# Sheet1.net
KiCad netlist of a schematic drawn in Altium Designer
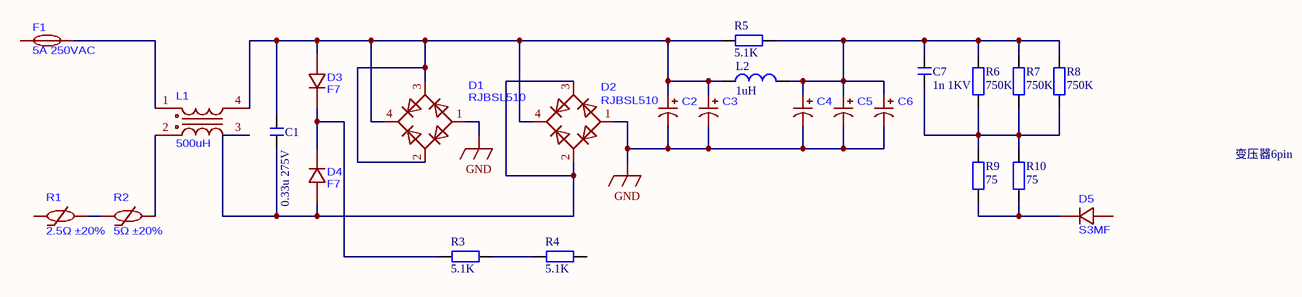
[diagram p0: Sheet1.SchDoc]

(export (version "E")
  (design (tool "Eeschema 10.0.6"))
  (components
    (comp (ref "C1")
      (value "0.33u 275V")
      (footprint "CAP-TH_L18.0-W8.5-P15.00-D0.8")
      (description "安规电容 X2 330nF ±10% 275V")
      (fields (field (name "PART_NUMBER") "MPX334K31D3KN15800"))
      (libsource (lib "自建库") (part "CAP"))
    )
    (comp (ref "C2")
      (value "33uF 400V")
      (footprint "CAP-TH_BD10.0-P5.00-D0.6-FD")
      (description "电解电容,33uF 400V\r\nC2914377\r\nC5183780/C781263")
      (fields (field (name "PART_NUMBER") "EKM2GM330G18OTBVZC"))
      (libsource (lib "自建库") (part "CAP_1"))
    )
    (comp (ref "C3")
      (value "33uF 400V")
      (footprint "CAP-TH_BD10.0-P5.00-D0.6-FD")
      (description "电解电容,33uF 400V\r\nC2914377\r\nC5183780/C781263")
      (fields (field (name "PART_NUMBER") "EKM2GM330G18OTBVZC"))
      (libsource (lib "自建库") (part "CAP_1"))
    )
    (comp (ref "C4")
      (value "33uF 400V")
      (footprint "CAP-TH_BD10.0-P5.00-D0.6-FD")
      (description "电解电容,33uF 400V\r\nC2914377\r\nC5183780/C781263")
      (fields (field (name "PART_NUMBER") "EKM2GM330G18OTBVZC"))
      (libsource (lib "自建库") (part "CAP_1"))
    )
    (comp (ref "C5")
      (value "33uF 400V")
      (footprint "CAP-TH_BD10.0-P5.00-D0.6-FD")
      (description "电解电容,33uF 400V\r\nC2914377\r\nC5183780/C781263")
      (fields (field (name "PART_NUMBER") "EKM2GM330G18OTBVZC"))
      (libsource (lib "自建库") (part "CAP_1"))
    )
    (comp (ref "C6")
      (value "33uF 400V")
      (footprint "CAP-TH_BD10.0-P5.00-D0.6-FD")
      (description "电解电容,33uF 400V\r\nC2914377\r\nC5183780/C781263")
      (fields (field (name "PART_NUMBER") "EKM2GM330G18OTBVZC"))
      (libsource (lib "自建库") (part "CAP_1"))
    )
    (comp (ref "C7")
      (value "1n 1KV")
      (footprint "C1206")
      (description "贴片电容,")
      (fields (field (name "PART_NUMBER") "CC1206KKX7RCBB102"))
      (libsource (lib "自建库") (part "CAP"))
    )
    (comp (ref "D1")
      (value "RJBSL510")
      (footprint "DIO-BG-SMD_4P-L4.9-W4.0-P2.54-LS7.0-BR")
      (description "整流桥，1KV，5A")
      (libsource (lib "自建库") (part "RJBSL510"))
    )
    (comp (ref "D2")
      (value "RJBSL510")
      (footprint "DIO-BG-SMD_4P-L4.9-W4.0-P2.54-LS7.0-BR")
      (description "整流桥，1KV，5A")
      (libsource (lib "自建库") (part "RJBSL510"))
    )
    (comp (ref "D3")
      (value "F7")
      (footprint "SOD-123_L2.7-W1.6-LS3.7-RD-1")
      (description "Diode,F7")
      (libsource (lib "自建库") (part "Diode"))
    )
    (comp (ref "D4")
      (value "F7")
      (footprint "SOD-123_L2.7-W1.6-LS3.7-RD-1")
      (description "Diode,F7")
      (libsource (lib "自建库") (part "Diode"))
    )
    (comp (ref "D5")
      (value "S3MF")
      (footprint "DO-214AC_L4.3-W2.7-LS5.2-RD")
      (description "Diode,S3MF")
      (libsource (lib "自建库") (part "Diode"))
    )
    (comp (ref "F1")
      (value "5A 250VAC")
      (footprint "FUSE-TH_L8.5-W4.0-P5.08-D0.6")
      (description "一次性保险丝，5A，250VAC\r\nC312477/C354906/C2839767")
      (fields (field (name "PART_NUMBER") "SET T5A 250V"))
      (libsource (lib "自建库") (part "Fuse"))
    )
    (comp (ref "L1")
      (value "500uH")
      (footprint "FILTER-TH_4P-L17.0-W12.0-P7.00-D0.6-S8.00-1")
      (description "共模滤波器，500uH\r\nC2923570")
      (fields (field (name "PART_NUMBER") "PDUUAT98-501MLN"))
      (libsource (lib "自建库") (part "Common mode Choke"))
    )
    (comp (ref "L2")
      (value "1uH")
      (footprint "IND-TH_BD10.5-P5.00-D0.6")
      (description "工字电感，22uH")
      (fields (field (name "PART_NUMBER") "XR9*12-220K-L"))
      (libsource (lib "自建库") (part "INDUCTOR"))
    )
    (comp (ref "R1")
      (value "2.5Ω ±20%")
      (footprint "RES-TH_L12.5-W5.1-P7.50-D1.2-S2.20")
      (description "NTC热敏电阻,2.5Ω,±20%,4A")
      (fields (field (name "PART_NUMBER") "R09D2R5MUB4CGWB"))
      (libsource (lib "自建库") (part "NTC"))
    )
    (comp (ref "R2")
      (value "5Ω ±20%")
      (footprint "RES-TH_L12.5-W5.1-P7.50-D1.2-S2.20")
      (description "NTC热敏电阻,5Ω,±20%,4A")
      (fields (field (name "PART_NUMBER") "R11D050MUB4CGWB"))
      (libsource (lib "自建库") (part "NTC"))
    )
    (comp (ref "R3")
      (value "5.1K")
      (footprint "R1206")
      (description "贴片电阻")
      (fields (field (name "PART_NUMBER") "RC1206JR-075K1L"))
      (libsource (lib "自建库") (part "RES"))
    )
    (comp (ref "R4")
      (value "5.1K")
      (footprint "R1206")
      (description "贴片电阻")
      (fields (field (name "PART_NUMBER") "RC1206JR-075K1L"))
      (libsource (lib "自建库") (part "RES"))
    )
    (comp (ref "R5")
      (value "5.1K")
      (footprint "R1206")
      (description "贴片电阻")
      (fields (field (name "PART_NUMBER") "RC1206JR-075K1L"))
      (libsource (lib "自建库") (part "RES"))
    )
    (comp (ref "R6")
      (value "750K")
      (footprint "R1206")
      (description "贴片电阻")
      (fields (field (name "PART_NUMBER") "RC1206JR-07750KL"))
      (libsource (lib "自建库") (part "RES"))
    )
    (comp (ref "R7")
      (value "750K")
      (footprint "R1206")
      (description "贴片电阻")
      (fields (field (name "PART_NUMBER") "RC1206JR-07750KL"))
      (libsource (lib "自建库") (part "RES"))
    )
    (comp (ref "R8")
      (value "750K")
      (footprint "R1206")
      (description "贴片电阻")
      (fields (field (name "PART_NUMBER") "RC1206JR-07750KL"))
      (libsource (lib "自建库") (part "RES"))
    )
    (comp (ref "R9")
      (value "75")
      (footprint "R1206")
      (description "贴片电阻")
      (fields (field (name "PART_NUMBER") "RC1206JR-0775RL"))
      (libsource (lib "自建库") (part "RES"))
    )
    (comp (ref "R10")
      (value "75")
      (footprint "R1206")
      (description "贴片电阻")
      (fields (field (name "PART_NUMBER") "RC1206JR-0775RL"))
      (libsource (lib "自建库") (part "RES"))
    )
  )
  (nets
    (net (code "1") (name "GND") (class "Default")
      (node (ref "C2") (pin "2") (pinfunction "2_2") (pintype "passive"))
      (node (ref "C3") (pin "2") (pinfunction "2_2") (pintype "passive"))
      (node (ref "C4") (pin "2") (pinfunction "2_2") (pintype "passive"))
      (node (ref "C5") (pin "2") (pinfunction "2_2") (pintype "passive"))
      (node (ref "C6") (pin "2") (pinfunction "2_2") (pintype "passive"))
      (node (ref "D1") (pin "1") (pinfunction "-_1") (pintype "passive"))
      (node (ref "D2") (pin "1") (pinfunction "-_1") (pintype "passive"))
    )
    (net (code "2") (name "Net-(C4-Pad1)") (class "Default")
      (node (ref "C4") (pin "1") (pinfunction "1_1") (pintype "passive"))
      (node (ref "C5") (pin "1") (pinfunction "1_1") (pintype "passive"))
      (node (ref "C6") (pin "1") (pinfunction "1_1") (pintype "passive"))
      (node (ref "C7") (pin "1") (pinfunction "1_1") (pintype "passive"))
      (node (ref "L2") (pin "2") (pinfunction "2_2") (pintype "passive"))
      (node (ref "R5") (pin "2") (pinfunction "2_2") (pintype "passive"))
      (node (ref "R6") (pin "2") (pinfunction "2_2") (pintype "passive"))
      (node (ref "R7") (pin "2") (pinfunction "2_2") (pintype "passive"))
      (node (ref "R8") (pin "2") (pinfunction "2_2") (pintype "passive"))
    )
    (net (code "3") (name "Net-(C7-Pad2)") (class "Default")
      (node (ref "C7") (pin "2") (pinfunction "2_2") (pintype "passive"))
      (node (ref "R10") (pin "2") (pinfunction "2_2") (pintype "passive"))
      (node (ref "R6") (pin "1") (pinfunction "1_1") (pintype "passive"))
      (node (ref "R7") (pin "1") (pinfunction "1_1") (pintype "passive"))
      (node (ref "R8") (pin "1") (pinfunction "1_1") (pintype "passive"))
      (node (ref "R9") (pin "2") (pinfunction "2_2") (pintype "passive"))
    )
    (net (code "4") (name "Net-(D1-+)") (class "Default")
      (node (ref "C1") (pin "2") (pinfunction "2_2") (pintype "passive"))
      (node (ref "C2") (pin "1") (pinfunction "1_1") (pintype "passive"))
      (node (ref "C3") (pin "1") (pinfunction "1_1") (pintype "passive"))
      (node (ref "D1") (pin "2") (pinfunction "C1_2") (pintype "passive"))
      (node (ref "D1") (pin "3") (pinfunction "C2_3") (pintype "passive"))
      (node (ref "D1") (pin "4") (pinfunction "+_4") (pintype "passive"))
      (node (ref "D2") (pin "4") (pinfunction "+_4") (pintype "passive"))
      (node (ref "D3") (pin "2") (pinfunction "+_2") (pintype "passive"))
      (node (ref "L1") (pin "4") (pinfunction "4_4") (pintype "passive"))
      (node (ref "L2") (pin "1") (pinfunction "1_1") (pintype "passive"))
      (node (ref "R5") (pin "1") (pinfunction "1_1") (pintype "passive"))
    )
    (net (code "5") (name "Net-(D2-C1)") (class "Default")
      (node (ref "C1") (pin "1") (pinfunction "1_1") (pintype "passive"))
      (node (ref "D2") (pin "2") (pinfunction "C1_2") (pintype "passive"))
      (node (ref "D2") (pin "3") (pinfunction "C2_3") (pintype "passive"))
      (node (ref "D4") (pin "2") (pinfunction "+_2") (pintype "passive"))
      (node (ref "L1") (pin "3") (pinfunction "3_3") (pintype "passive"))
    )
    (net (code "6") (name "Net-(D3--)") (class "Default")
      (node (ref "D3") (pin "1") (pinfunction "-_1") (pintype "passive"))
      (node (ref "D4") (pin "1") (pinfunction "-_1") (pintype "passive"))
      (node (ref "R3") (pin "1") (pinfunction "1_1") (pintype "passive"))
    )
    (net (code "7") (name "Net-(D5--)") (class "Default")
      (node (ref "D5") (pin "1") (pinfunction "-_1") (pintype "passive"))
      (node (ref "R10") (pin "1") (pinfunction "1_1") (pintype "passive"))
      (node (ref "R9") (pin "1") (pinfunction "1_1") (pintype "passive"))
    )
    (net (code "8") (name "Net-(F1-Pad2)") (class "Default")
      (node (ref "F1") (pin "2") (pinfunction "2_2") (pintype "passive"))
      (node (ref "L1") (pin "1") (pinfunction "1_1") (pintype "passive"))
    )
    (net (code "9") (name "Net-(L1-Pad2)") (class "Default")
      (node (ref "L1") (pin "2") (pinfunction "2_2") (pintype "passive"))
      (node (ref "R2") (pin "2") (pinfunction "2_2") (pintype "passive"))
    )
    (net (code "10") (name "Net-(R1-Pad2)") (class "Default")
      (node (ref "R1") (pin "2") (pinfunction "2_2") (pintype "passive"))
      (node (ref "R2") (pin "1") (pinfunction "1_1") (pintype "passive"))
    )
    (net (code "11") (name "Net-(R3-Pad2)") (class "Default")
      (node (ref "R3") (pin "2") (pinfunction "2_2") (pintype "passive"))
      (node (ref "R4") (pin "1") (pinfunction "1_1") (pintype "passive"))
    )
    (net (code "12") (name "unconnected-(D5-+-Pad2)") (class "Default")
      (node (ref "D5") (pin "2") (pinfunction "+_2") (pintype "passive"))
    )
    (net (code "13") (name "unconnected-(F1-Pad1)") (class "Default")
      (node (ref "F1") (pin "1") (pinfunction "1_1") (pintype "passive"))
    )
    (net (code "14") (name "unconnected-(R1-Pad1)") (class "Default")
      (node (ref "R1") (pin "1") (pinfunction "1_1") (pintype "passive"))
    )
    (net (code "15") (name "unconnected-(R4-Pad2)") (class "Default")
      (node (ref "R4") (pin "2") (pinfunction "2_2") (pintype "passive"))
    )
  )
)
